# qspi-flash.net
KiCad netlist of a schematic drawn in Altium Designer
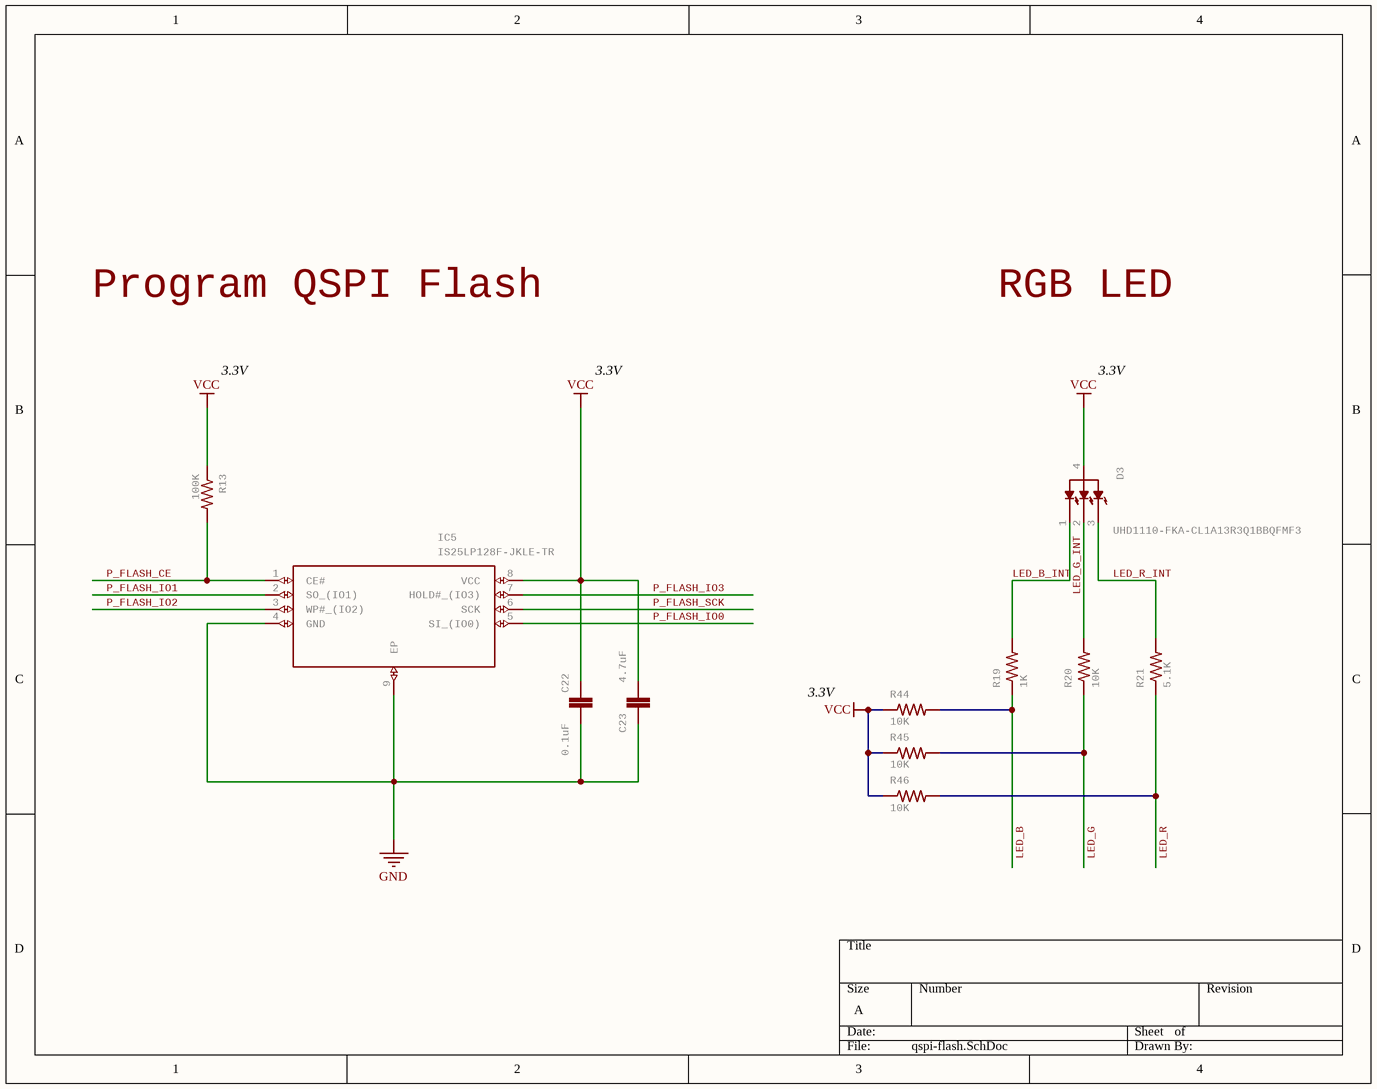
[diagram p0: qspi-flash.SchDoc]

(export (version "E")
  (design (tool "Eeschema 10.0.6"))
  (components
    (comp (ref "C22")
      (value "0.1uF")
      (footprint "0402-CAP")
      (description "CAPACITOR, European symbol")
      (fields (field (name "MPN") "C0402C104Z4VAC"))
      (libsource (lib "rt10") (part "C-EUC0201"))
    )
    (comp (ref "C23")
      (value "4.7uF")
      (footprint "0402-CAP")
      (description "CapacitorStandard 0603 ceramic capacitor, and 0.1\" leaded capacitor.")
      (fields (field (name "MPN") "JMK105BBJ475MV-F"))
      (libsource (lib "rt10") (part "CAP0402-CAP"))
    )
    (comp (ref "D3")
      (value "UHD1110-FKA-CL1A13R3Q1BBQFMF3")
      (footprint "LED_UHD1110-FKA-CL1A13R3Q1BBQFMF3")
      (description "LED RGB SMD, SIZE 1 X 1 mm Check availability")
      (fields (field (name "MF") "Cree Inc.") (field (name "MPN") "UHD1110-FKA-CL1A13r3q1BBQFMF3"))
      (libsource (lib "rt10") (part "UHD1110-FKA-CL1A13R3Q1BBQFMF3"))
    )
    (comp (ref "IC5")
      (value "IS25LP128F-JKLE-TR")
      (footprint "SON127P500X595X80-9N")
      (description "NOR Flash 128M 2.3-3.6V 166Mhz Serial NOR Flash   Source:  Datasheet")
      (fields (field (name "MOUSER_PART_NUMBER") "870-IS25LP128F-JKLE-TR"))
      (libsource (lib "rt10") (part "IS25LP128F-JKLE-TR"))
    )
    (comp (ref "R13")
      (value "100K")
      (footprint "0402-RES")
      (description "ResistorBasic schematic elements and footprints for 0603, 1206, and PTH resistors.")
      (fields (field (name "MPN") "AC0402FR-07100KL"))
      (libsource (lib "rt10") (part "RESISTOR0402-RES"))
    )
    (comp (ref "R19")
      (value "1K")
      (footprint "0402-RES")
      (description "ResistorBasic schematic elements and footprints for 0603, 1206, and PTH resistors.")
      (fields (field (name "MPN") "CRCW04021K00FKEDC"))
      (libsource (lib "rt10") (part "RESISTOR0402-RES"))
    )
    (comp (ref "R20")
      (value "10K")
      (footprint "0402-RES")
      (description "ResistorBasic schematic elements and footprints for 0603, 1206, and PTH resistors.")
      (fields (field (name "MPN") "AC0402FR-1310KL"))
      (libsource (lib "rt10") (part "RESISTOR0402-RES"))
    )
    (comp (ref "R21")
      (value "5.1K")
      (footprint "0402-RES")
      (description "ResistorBasic schematic elements and footprints for 0603, 1206, and PTH resistors.")
      (fields (field (name "MPN") "RC0402JR-075K1L"))
      (libsource (lib "rt10") (part "RESISTOR0402-RES"))
    )
    (comp (ref "R44")
      (value "10K")
      (footprint "0402-RES")
      (description "ResistorBasic schematic elements and footprints for 0603, 1206, and PTH resistors.")
      (fields (field (name "MPN") "AC0402FR-1310KL"))
      (libsource (lib "rt10") (part "RESISTOR0402-RES"))
    )
    (comp (ref "R45")
      (value "10K")
      (footprint "0402-RES")
      (description "ResistorBasic schematic elements and footprints for 0603, 1206, and PTH resistors.")
      (fields (field (name "MPN") "AC0402FR-1310KL"))
      (libsource (lib "rt10") (part "RESISTOR0402-RES"))
    )
    (comp (ref "R46")
      (value "10K")
      (footprint "0402-RES")
      (description "ResistorBasic schematic elements and footprints for 0603, 1206, and PTH resistors.")
      (fields (field (name "MPN") "AC0402FR-1310KL"))
      (libsource (lib "rt10") (part "RESISTOR0402-RES"))
    )
  )
  (nets
    (net (code "1") (name "/LED_B") (class "Default")
      (node (ref "R19") (pin "1") (pinfunction "1_1") (pintype "passive"))
      (node (ref "R44") (pin "2") (pinfunction "2_2") (pintype "passive"))
    )
    (net (code "2") (name "/LED_B_INT") (class "Default")
      (node (ref "D3") (pin "1") (pinfunction "BLUE_1") (pintype "passive"))
      (node (ref "R19") (pin "2") (pinfunction "2_2") (pintype "passive"))
    )
    (net (code "3") (name "/LED_G") (class "Default")
      (node (ref "R20") (pin "1") (pinfunction "1_1") (pintype "passive"))
      (node (ref "R45") (pin "2") (pinfunction "2_2") (pintype "passive"))
    )
    (net (code "4") (name "/LED_G_INT") (class "Default")
      (node (ref "D3") (pin "2") (pinfunction "GREEN_2") (pintype "passive"))
      (node (ref "R20") (pin "2") (pinfunction "2_2") (pintype "passive"))
    )
    (net (code "5") (name "/LED_R") (class "Default")
      (node (ref "R21") (pin "1") (pinfunction "1_1") (pintype "passive"))
      (node (ref "R46") (pin "2") (pinfunction "2_2") (pintype "passive"))
    )
    (net (code "6") (name "/LED_R_INT") (class "Default")
      (node (ref "D3") (pin "3") (pinfunction "RED_3") (pintype "passive"))
      (node (ref "R21") (pin "2") (pinfunction "2_2") (pintype "passive"))
    )
    (net (code "7") (name "/P_FLASH_CE") (class "Default")
      (node (ref "IC5") (pin "1") (pinfunction "CE#_1") (pintype "bidirectional"))
      (node (ref "R13") (pin "2") (pinfunction "2_2") (pintype "passive"))
    )
    (net (code "8") (name "/P_FLASH_IO0") (class "Default")
      (node (ref "IC5") (pin "5") (pinfunction "SI_(IO0)_5") (pintype "bidirectional"))
    )
    (net (code "9") (name "/P_FLASH_IO1") (class "Default")
      (node (ref "IC5") (pin "2") (pinfunction "SO_(IO1)_2") (pintype "bidirectional"))
    )
    (net (code "10") (name "/P_FLASH_IO2") (class "Default")
      (node (ref "IC5") (pin "3") (pinfunction "WP#_(IO2)_3") (pintype "bidirectional"))
    )
    (net (code "11") (name "/P_FLASH_IO3") (class "Default")
      (node (ref "IC5") (pin "7") (pinfunction "HOLD#_(IO3)_7") (pintype "bidirectional"))
    )
    (net (code "12") (name "/P_FLASH_SCK") (class "Default")
      (node (ref "IC5") (pin "6") (pinfunction "SCK_6") (pintype "bidirectional"))
    )
    (net (code "13") (name "GND") (class "Default")
      (node (ref "C22") (pin "2") (pinfunction "2_2") (pintype "passive"))
      (node (ref "C23") (pin "1") (pinfunction "1_1") (pintype "passive"))
      (node (ref "IC5") (pin "4") (pinfunction "GND_4") (pintype "bidirectional"))
      (node (ref "IC5") (pin "9") (pinfunction "EP_9") (pintype "bidirectional"))
    )
    (net (code "14") (name "VCC") (class "Default")
      (node (ref "C22") (pin "1") (pinfunction "1_1") (pintype "passive"))
      (node (ref "C23") (pin "2") (pinfunction "2_2") (pintype "passive"))
      (node (ref "D3") (pin "4") (pinfunction "ANODE_4") (pintype "passive"))
      (node (ref "IC5") (pin "8") (pinfunction "VCC_8") (pintype "bidirectional"))
      (node (ref "R13") (pin "1") (pinfunction "1_1") (pintype "passive"))
      (node (ref "R44") (pin "1") (pinfunction "1_1") (pintype "passive"))
      (node (ref "R45") (pin "1") (pinfunction "1_1") (pintype "passive"))
      (node (ref "R46") (pin "1") (pinfunction "1_1") (pintype "passive"))
    )
  )
)
